# advanced.net
KiCad netlist of a schematic drawn in EAGLE
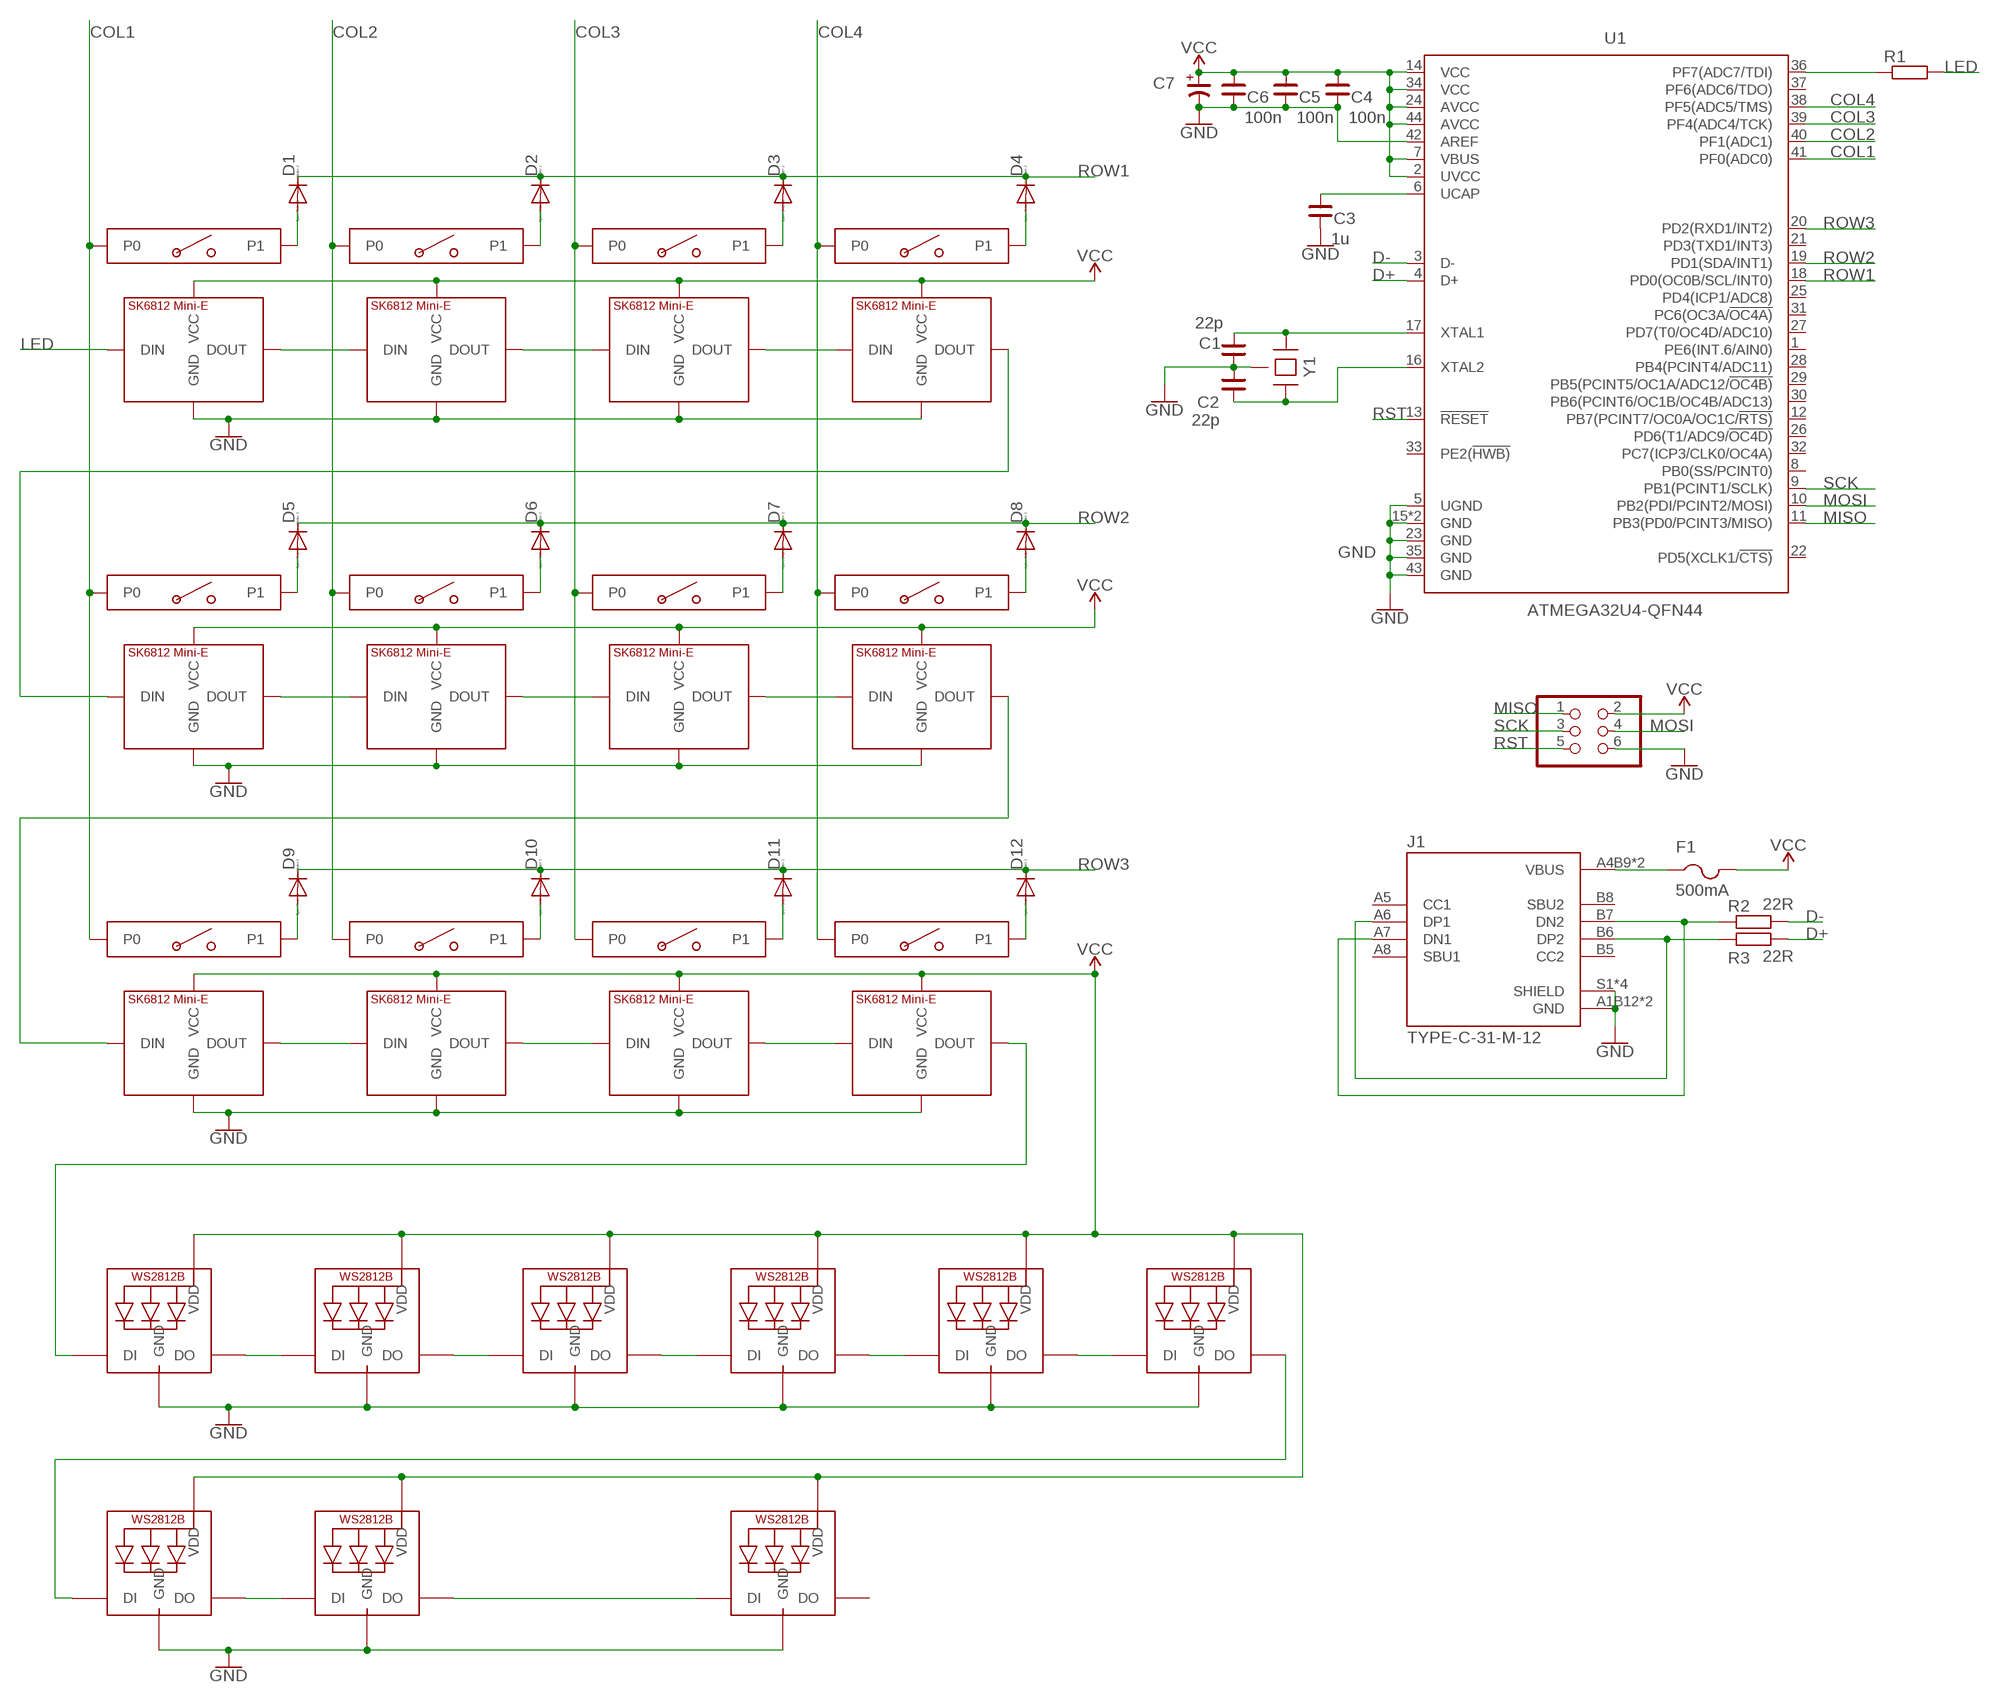
[diagram p0: schematic, sheet 1]

(export (version "E")
  (design (tool "Eeschema 10.0.6"))
  (components
    (comp (ref "C1")
      (value "22p")
      (footprint "eagle-import:0805")
      (libsource (lib "eagle-import") (part "CNP-0805"))
    )
    (comp (ref "C2")
      (value "22p")
      (footprint "eagle-import:0805")
      (libsource (lib "eagle-import") (part "CNP-0805"))
    )
    (comp (ref "C3")
      (value "1u")
      (footprint "eagle-import:0805")
      (libsource (lib "eagle-import") (part "CNP-0805"))
    )
    (comp (ref "C4")
      (value "100n")
      (footprint "eagle-import:0805")
      (libsource (lib "eagle-import") (part "CNP-0805"))
    )
    (comp (ref "C5")
      (value "100n")
      (footprint "eagle-import:0805")
      (libsource (lib "eagle-import") (part "CNP-0805"))
    )
    (comp (ref "C6")
      (value "100n")
      (footprint "eagle-import:0805")
      (libsource (lib "eagle-import") (part "CNP-0805"))
    )
    (comp (ref "C7")
      (value "10u")
      (footprint "eagle-import:3216-18R_T")
      (libsource (lib "eagle-import") (part "CP-3216-18R"))
    )
    (comp (ref "D1")
      (value "1N4148DIODE_0805")
      (footprint "eagle-import:0805")
      (libsource (lib "eagle-import") (part "1N4148DIODE_0805"))
    )
    (comp (ref "D2")
      (value "1N4148DIODE_0805")
      (footprint "eagle-import:0805")
      (libsource (lib "eagle-import") (part "1N4148DIODE_0805"))
    )
    (comp (ref "D3")
      (value "1N4148DIODE_0805")
      (footprint "eagle-import:0805")
      (libsource (lib "eagle-import") (part "1N4148DIODE_0805"))
    )
    (comp (ref "D4")
      (value "1N4148DIODE_0805")
      (footprint "eagle-import:0805")
      (libsource (lib "eagle-import") (part "1N4148DIODE_0805"))
    )
    (comp (ref "D5")
      (value "1N4148DIODE_0805")
      (footprint "eagle-import:0805")
      (libsource (lib "eagle-import") (part "1N4148DIODE_0805"))
    )
    (comp (ref "D6")
      (value "1N4148DIODE_0805")
      (footprint "eagle-import:0805")
      (libsource (lib "eagle-import") (part "1N4148DIODE_0805"))
    )
    (comp (ref "D7")
      (value "1N4148DIODE_0805")
      (footprint "eagle-import:0805")
      (libsource (lib "eagle-import") (part "1N4148DIODE_0805"))
    )
    (comp (ref "D8")
      (value "1N4148DIODE_0805")
      (footprint "eagle-import:0805")
      (libsource (lib "eagle-import") (part "1N4148DIODE_0805"))
    )
    (comp (ref "D9")
      (value "1N4148DIODE_0805")
      (footprint "eagle-import:0805")
      (libsource (lib "eagle-import") (part "1N4148DIODE_0805"))
    )
    (comp (ref "D10")
      (value "1N4148DIODE_0805")
      (footprint "eagle-import:0805")
      (libsource (lib "eagle-import") (part "1N4148DIODE_0805"))
    )
    (comp (ref "D11")
      (value "1N4148DIODE_0805")
      (footprint "eagle-import:0805")
      (libsource (lib "eagle-import") (part "1N4148DIODE_0805"))
    )
    (comp (ref "D12")
      (value "1N4148DIODE_0805")
      (footprint "eagle-import:0805")
      (libsource (lib "eagle-import") (part "1N4148DIODE_0805"))
    )
    (comp (ref "F1")
      (value "500mA")
      (footprint "eagle-import:R1206")
      (libsource (lib "eagle-import") (part "PTCFUSE-1206"))
    )
    (comp (ref "J1")
      (value "TYPE-C-31-M-12")
      (footprint "eagle-import:HRO_TYPE-C-31-M-12")
      (fields (field (name "MF") "HRO Electronics Co., Ltd."))
      (libsource (lib "eagle-import") (part "TYPE-C-31-M-12"))
    )
    (comp (ref "JP3")
      (value "PINHD-2X3")
      (footprint "eagle-import:2X03")
      (libsource (lib "eagle-import") (part "PINHD-2X3"))
    )
    (comp (ref "R1")
      (value "RESISTOR-0805")
      (footprint "eagle-import:R0805")
      (libsource (lib "eagle-import") (part "RESISTOR-0805"))
    )
    (comp (ref "R2")
      (value "22R")
      (footprint "eagle-import:R0805")
      (libsource (lib "eagle-import") (part "RESISTOR-0805"))
    )
    (comp (ref "R3")
      (value "22R")
      (footprint "eagle-import:R0805")
      (libsource (lib "eagle-import") (part "RESISTOR-0805"))
    )
    (comp (ref "U$1")
      (value "WS2812B-3535")
      (footprint "eagle-import:3535-LED")
      (libsource (lib "eagle-import") (part "WS2812B-3535"))
    )
    (comp (ref "U$2")
      (value "WS2812B-3535")
      (footprint "eagle-import:3535-LED")
      (libsource (lib "eagle-import") (part "WS2812B-3535"))
    )
    (comp (ref "U$3")
      (value "WS2812B-3535")
      (footprint "eagle-import:3535-LED")
      (libsource (lib "eagle-import") (part "WS2812B-3535"))
    )
    (comp (ref "U$4")
      (value "WS2812B-3535")
      (footprint "eagle-import:3535-LED")
      (libsource (lib "eagle-import") (part "WS2812B-3535"))
    )
    (comp (ref "U$5")
      (value "WS2812B-3535")
      (footprint "eagle-import:3535-LED")
      (libsource (lib "eagle-import") (part "WS2812B-3535"))
    )
    (comp (ref "U$6")
      (value "WS2812B-3535")
      (footprint "eagle-import:3535-LED")
      (libsource (lib "eagle-import") (part "WS2812B-3535"))
    )
    (comp (ref "U$7")
      (value "WS2812B-3535")
      (footprint "eagle-import:3535-LED")
      (libsource (lib "eagle-import") (part "WS2812B-3535"))
    )
    (comp (ref "U$8")
      (value "WS2812B-3535")
      (footprint "eagle-import:3535-LED")
      (libsource (lib "eagle-import") (part "WS2812B-3535"))
    )
    (comp (ref "U$10")
      (value "WS2812B-3535")
      (footprint "eagle-import:3535-LED")
      (libsource (lib "eagle-import") (part "WS2812B-3535"))
    )
    (comp (ref "U$55")
      (value "KEYSWITCH-SK6812")
      (footprint "eagle-import:UNIVERSAL_KEYSWITCH_SK6812MINIE")
      (libsource (lib "eagle-import") (part "KEYSWITCH-SK6812"))
    )
    (comp (ref "U$57")
      (value "KEYSWITCH-SK6812")
      (footprint "eagle-import:UNIVERSAL_KEYSWITCH_SK6812MINIE")
      (libsource (lib "eagle-import") (part "KEYSWITCH-SK6812"))
    )
    (comp (ref "U$59")
      (value "KEYSWITCH-SK6812")
      (footprint "eagle-import:UNIVERSAL_KEYSWITCH_SK6812MINIE")
      (libsource (lib "eagle-import") (part "KEYSWITCH-SK6812"))
    )
    (comp (ref "U$61")
      (value "KEYSWITCH-SK6812")
      (footprint "eagle-import:UNIVERSAL_KEYSWITCH_SK6812MINIE")
      (libsource (lib "eagle-import") (part "KEYSWITCH-SK6812"))
    )
    (comp (ref "U$73")
      (value "KEYSWITCH-SK6812")
      (footprint "eagle-import:UNIVERSAL_KEYSWITCH_SK6812MINIE")
      (libsource (lib "eagle-import") (part "KEYSWITCH-SK6812"))
    )
    (comp (ref "U$75")
      (value "KEYSWITCH-SK6812")
      (footprint "eagle-import:UNIVERSAL_KEYSWITCH_SK6812MINIE")
      (libsource (lib "eagle-import") (part "KEYSWITCH-SK6812"))
    )
    (comp (ref "U$77")
      (value "KEYSWITCH-SK6812")
      (footprint "eagle-import:UNIVERSAL_KEYSWITCH_SK6812MINIE")
      (libsource (lib "eagle-import") (part "KEYSWITCH-SK6812"))
    )
    (comp (ref "U$79")
      (value "KEYSWITCH-SK6812")
      (footprint "eagle-import:UNIVERSAL_KEYSWITCH_SK6812MINIE")
      (libsource (lib "eagle-import") (part "KEYSWITCH-SK6812"))
    )
    (comp (ref "U$91")
      (value "KEYSWITCH-SK6812")
      (footprint "eagle-import:UNIVERSAL_KEYSWITCH_SK6812MINIE")
      (libsource (lib "eagle-import") (part "KEYSWITCH-SK6812"))
    )
    (comp (ref "U$93")
      (value "KEYSWITCH-SK6812")
      (footprint "eagle-import:UNIVERSAL_KEYSWITCH_SK6812MINIE")
      (libsource (lib "eagle-import") (part "KEYSWITCH-SK6812"))
    )
    (comp (ref "U$95")
      (value "KEYSWITCH-SK6812")
      (footprint "eagle-import:UNIVERSAL_KEYSWITCH_SK6812MINIE")
      (libsource (lib "eagle-import") (part "KEYSWITCH-SK6812"))
    )
    (comp (ref "U$97")
      (value "KEYSWITCH-SK6812")
      (footprint "eagle-import:UNIVERSAL_KEYSWITCH_SK6812MINIE")
      (libsource (lib "eagle-import") (part "KEYSWITCH-SK6812"))
    )
    (comp (ref "U1")
      (value "ATMEGA32U4-QFN44")
      (footprint "eagle-import:QFN-44")
      (libsource (lib "eagle-import") (part "ATMEGA32U4-QFN44"))
    )
    (comp (ref "Y1")
      (value "CRYSTAL-4PIN-3.2X2.5")
      (footprint "eagle-import:CRYSTAL-3.2X2.5")
      (libsource (lib "eagle-import") (part "CRYSTAL-4PIN-3.2X2.5"))
    )
  )
  (nets
    (net (code "1") (name "/COL1") (class "Default")
      (node (ref "U$55") (pin "ALPS1") (pinfunction "P0_ALPS1") (pintype "bidirectional"))
      (node (ref "U$55") (pin "CHOC1") (pinfunction "P0_CHOC1") (pintype "bidirectional"))
      (node (ref "U$55") (pin "MX1") (pinfunction "P0_MX1") (pintype "bidirectional"))
      (node (ref "U$73") (pin "ALPS1") (pinfunction "P0_ALPS1") (pintype "bidirectional"))
      (node (ref "U$73") (pin "CHOC1") (pinfunction "P0_CHOC1") (pintype "bidirectional"))
      (node (ref "U$73") (pin "MX1") (pinfunction "P0_MX1") (pintype "bidirectional"))
      (node (ref "U$91") (pin "ALPS1") (pinfunction "P0_ALPS1") (pintype "bidirectional"))
      (node (ref "U$91") (pin "CHOC1") (pinfunction "P0_CHOC1") (pintype "bidirectional"))
      (node (ref "U$91") (pin "MX1") (pinfunction "P0_MX1") (pintype "bidirectional"))
      (node (ref "U1") (pin "41") (pinfunction "PF0(ADC0)_41") (pintype "bidirectional"))
    )
    (net (code "2") (name "/COL2") (class "Default")
      (node (ref "U$57") (pin "ALPS1") (pinfunction "P0_ALPS1") (pintype "bidirectional"))
      (node (ref "U$57") (pin "CHOC1") (pinfunction "P0_CHOC1") (pintype "bidirectional"))
      (node (ref "U$57") (pin "MX1") (pinfunction "P0_MX1") (pintype "bidirectional"))
      (node (ref "U$75") (pin "ALPS1") (pinfunction "P0_ALPS1") (pintype "bidirectional"))
      (node (ref "U$75") (pin "CHOC1") (pinfunction "P0_CHOC1") (pintype "bidirectional"))
      (node (ref "U$75") (pin "MX1") (pinfunction "P0_MX1") (pintype "bidirectional"))
      (node (ref "U$93") (pin "ALPS1") (pinfunction "P0_ALPS1") (pintype "bidirectional"))
      (node (ref "U$93") (pin "CHOC1") (pinfunction "P0_CHOC1") (pintype "bidirectional"))
      (node (ref "U$93") (pin "MX1") (pinfunction "P0_MX1") (pintype "bidirectional"))
      (node (ref "U1") (pin "40") (pinfunction "PF1(ADC1)_40") (pintype "bidirectional"))
    )
    (net (code "3") (name "/COL3") (class "Default")
      (node (ref "U$59") (pin "ALPS1") (pinfunction "P0_ALPS1") (pintype "bidirectional"))
      (node (ref "U$59") (pin "CHOC1") (pinfunction "P0_CHOC1") (pintype "bidirectional"))
      (node (ref "U$59") (pin "MX1") (pinfunction "P0_MX1") (pintype "bidirectional"))
      (node (ref "U$77") (pin "ALPS1") (pinfunction "P0_ALPS1") (pintype "bidirectional"))
      (node (ref "U$77") (pin "CHOC1") (pinfunction "P0_CHOC1") (pintype "bidirectional"))
      (node (ref "U$77") (pin "MX1") (pinfunction "P0_MX1") (pintype "bidirectional"))
      (node (ref "U$95") (pin "ALPS1") (pinfunction "P0_ALPS1") (pintype "bidirectional"))
      (node (ref "U$95") (pin "CHOC1") (pinfunction "P0_CHOC1") (pintype "bidirectional"))
      (node (ref "U$95") (pin "MX1") (pinfunction "P0_MX1") (pintype "bidirectional"))
      (node (ref "U1") (pin "39") (pinfunction "PF4(ADC4/TCK)_39") (pintype "bidirectional"))
    )
    (net (code "4") (name "/COL4") (class "Default")
      (node (ref "U$61") (pin "ALPS1") (pinfunction "P0_ALPS1") (pintype "bidirectional"))
      (node (ref "U$61") (pin "CHOC1") (pinfunction "P0_CHOC1") (pintype "bidirectional"))
      (node (ref "U$61") (pin "MX1") (pinfunction "P0_MX1") (pintype "bidirectional"))
      (node (ref "U$79") (pin "ALPS1") (pinfunction "P0_ALPS1") (pintype "bidirectional"))
      (node (ref "U$79") (pin "CHOC1") (pinfunction "P0_CHOC1") (pintype "bidirectional"))
      (node (ref "U$79") (pin "MX1") (pinfunction "P0_MX1") (pintype "bidirectional"))
      (node (ref "U$97") (pin "ALPS1") (pinfunction "P0_ALPS1") (pintype "bidirectional"))
      (node (ref "U$97") (pin "CHOC1") (pinfunction "P0_CHOC1") (pintype "bidirectional"))
      (node (ref "U$97") (pin "MX1") (pinfunction "P0_MX1") (pintype "bidirectional"))
      (node (ref "U1") (pin "38") (pinfunction "PF5(ADC5/TMS)_38") (pintype "bidirectional"))
    )
    (net (code "5") (name "/D+") (class "Default")
      (node (ref "R3") (pin "2") (pinfunction "2_2") (pintype "passive"))
      (node (ref "U1") (pin "4") (pinfunction "D+_4") (pintype "bidirectional"))
    )
    (net (code "6") (name "/D-") (class "Default")
      (node (ref "R2") (pin "2") (pinfunction "2_2") (pintype "passive"))
      (node (ref "U1") (pin "3") (pinfunction "D-_3") (pintype "bidirectional"))
    )
    (net (code "7") (name "/LED") (class "Default")
      (node (ref "R1") (pin "2") (pinfunction "2_2") (pintype "passive"))
      (node (ref "U$91") (pin "DIN") (pinfunction "DIN_DIN") (pintype "bidirectional"))
    )
    (net (code "8") (name "/MISO") (class "Default")
      (node (ref "JP3") (pin "1") (pinfunction "1_1") (pintype "passive"))
      (node (ref "U1") (pin "11") (pinfunction "PB3(PD0/PCINT3/MISO)_11") (pintype "bidirectional"))
    )
    (net (code "9") (name "/MOSI") (class "Default")
      (node (ref "JP3") (pin "4") (pinfunction "4_4") (pintype "passive"))
      (node (ref "U1") (pin "10") (pinfunction "PB2(PDI/PCINT2/MOSI)_10") (pintype "bidirectional"))
    )
    (net (code "10") (name "/ROW1") (class "Default")
      (node (ref "D1") (pin "2") (pinfunction "C_2") (pintype "passive"))
      (node (ref "D2") (pin "2") (pinfunction "C_2") (pintype "passive"))
      (node (ref "D3") (pin "2") (pinfunction "C_2") (pintype "passive"))
      (node (ref "D4") (pin "2") (pinfunction "C_2") (pintype "passive"))
      (node (ref "U1") (pin "18") (pinfunction "PD0(OC0B/SCL/INT0)_18") (pintype "bidirectional"))
    )
    (net (code "11") (name "/ROW2") (class "Default")
      (node (ref "D5") (pin "2") (pinfunction "C_2") (pintype "passive"))
      (node (ref "D6") (pin "2") (pinfunction "C_2") (pintype "passive"))
      (node (ref "D7") (pin "2") (pinfunction "C_2") (pintype "passive"))
      (node (ref "D8") (pin "2") (pinfunction "C_2") (pintype "passive"))
      (node (ref "U1") (pin "19") (pinfunction "PD1(SDA/INT1)_19") (pintype "bidirectional"))
    )
    (net (code "12") (name "/ROW3") (class "Default")
      (node (ref "D10") (pin "2") (pinfunction "C_2") (pintype "passive"))
      (node (ref "D11") (pin "2") (pinfunction "C_2") (pintype "passive"))
      (node (ref "D12") (pin "2") (pinfunction "C_2") (pintype "passive"))
      (node (ref "D9") (pin "2") (pinfunction "C_2") (pintype "passive"))
      (node (ref "U1") (pin "20") (pinfunction "PD2(RXD1/INT2)_20") (pintype "bidirectional"))
    )
    (net (code "13") (name "/RST") (class "Default")
      (node (ref "JP3") (pin "5") (pinfunction "5_5") (pintype "passive"))
      (node (ref "U1") (pin "13") (pinfunction "~{RESET}_13") (pintype "bidirectional"))
    )
    (net (code "14") (name "/SCK") (class "Default")
      (node (ref "JP3") (pin "3") (pinfunction "3_3") (pintype "passive"))
      (node (ref "U1") (pin "9") (pinfunction "PB1(PCINT1/SCLK)_9") (pintype "bidirectional"))
    )
    (net (code "15") (name "GND") (class "Default")
      (node (ref "C1") (pin "1") (pinfunction "1_1") (pintype "passive"))
      (node (ref "C2") (pin "2") (pinfunction "2_2") (pintype "passive"))
      (node (ref "C3") (pin "2") (pinfunction "2_2") (pintype "passive"))
      (node (ref "C4") (pin "2") (pinfunction "2_2") (pintype "passive"))
      (node (ref "C5") (pin "2") (pinfunction "2_2") (pintype "passive"))
      (node (ref "C6") (pin "2") (pinfunction "2_2") (pintype "passive"))
      (node (ref "C7") (pin "-") (pinfunction "-_-") (pintype "passive"))
      (node (ref "J1") (pin "A1B12") (pinfunction "GND_A1B12") (pintype "power_in"))
      (node (ref "J1") (pin "B1A12") (pinfunction "GND_B1A12") (pintype "power_in"))
      (node (ref "J1") (pin "S1") (pinfunction "SHIELD_S1") (pintype "passive"))
      (node (ref "J1") (pin "S2") (pinfunction "SHIELD_S2") (pintype "passive"))
      (node (ref "J1") (pin "S3") (pinfunction "SHIELD_S3") (pintype "passive"))
      (node (ref "J1") (pin "S4") (pinfunction "SHIELD_S4") (pintype "passive"))
      (node (ref "JP3") (pin "6") (pinfunction "6_6") (pintype "passive"))
      (node (ref "U$1") (pin "GND") (pinfunction "GND_GND") (pintype "power_in"))
      (node (ref "U$10") (pin "GND") (pinfunction "GND_GND") (pintype "power_in"))
      (node (ref "U$2") (pin "GND") (pinfunction "GND_GND") (pintype "power_in"))
      (node (ref "U$3") (pin "GND") (pinfunction "GND_GND") (pintype "power_in"))
      (node (ref "U$4") (pin "GND") (pinfunction "GND_GND") (pintype "power_in"))
      (node (ref "U$5") (pin "GND") (pinfunction "GND_GND") (pintype "power_in"))
      (node (ref "U$55") (pin "GND") (pinfunction "GND_GND") (pintype "bidirectional"))
      (node (ref "U$57") (pin "GND") (pinfunction "GND_GND") (pintype "bidirectional"))
      (node (ref "U$59") (pin "GND") (pinfunction "GND_GND") (pintype "bidirectional"))
      (node (ref "U$6") (pin "GND") (pinfunction "GND_GND") (pintype "power_in"))
      (node (ref "U$61") (pin "GND") (pinfunction "GND_GND") (pintype "bidirectional"))
      (node (ref "U$7") (pin "GND") (pinfunction "GND_GND") (pintype "power_in"))
      (node (ref "U$73") (pin "GND") (pinfunction "GND_GND") (pintype "bidirectional"))
      (node (ref "U$75") (pin "GND") (pinfunction "GND_GND") (pintype "bidirectional"))
      (node (ref "U$77") (pin "GND") (pinfunction "GND_GND") (pintype "bidirectional"))
      (node (ref "U$79") (pin "GND") (pinfunction "GND_GND") (pintype "bidirectional"))
      (node (ref "U$8") (pin "GND") (pinfunction "GND_GND") (pintype "power_in"))
      (node (ref "U$91") (pin "GND") (pinfunction "GND_GND") (pintype "bidirectional"))
      (node (ref "U$93") (pin "GND") (pinfunction "GND_GND") (pintype "bidirectional"))
      (node (ref "U$95") (pin "GND") (pinfunction "GND_GND") (pintype "bidirectional"))
      (node (ref "U$97") (pin "GND") (pinfunction "GND_GND") (pintype "bidirectional"))
      (node (ref "U1") (pin "15") (pinfunction "GND_15") (pintype "bidirectional"))
      (node (ref "U1") (pin "23") (pinfunction "GND_23") (pintype "bidirectional"))
      (node (ref "U1") (pin "35") (pinfunction "GND_35") (pintype "bidirectional"))
      (node (ref "U1") (pin "42") (pinfunction "AREF_42") (pintype "bidirectional"))
      (node (ref "U1") (pin "43") (pinfunction "GND_43") (pintype "bidirectional"))
      (node (ref "U1") (pin "5") (pinfunction "UGND_5") (pintype "bidirectional"))
      (node (ref "U1") (pin "TAB") (pinfunction "GND_TAB") (pintype "bidirectional"))
      (node (ref "Y1") (pin "2") (pinfunction "GND_2") (pintype "bidirectional"))
      (node (ref "Y1") (pin "4") (pinfunction "GND_4") (pintype "bidirectional"))
    )
    (net (code "16") (name "Net-(D1-A)") (class "Default")
      (node (ref "D1") (pin "1") (pinfunction "A_1") (pintype "passive"))
      (node (ref "U$91") (pin "ALPS2") (pinfunction "P1_ALPS2") (pintype "bidirectional"))
      (node (ref "U$91") (pin "CHOC2") (pinfunction "P1_CHOC2") (pintype "bidirectional"))
      (node (ref "U$91") (pin "MX2") (pinfunction "P1_MX2") (pintype "bidirectional"))
    )
    (net (code "17") (name "Net-(D2-A)") (class "Default")
      (node (ref "D2") (pin "1") (pinfunction "A_1") (pintype "passive"))
      (node (ref "U$93") (pin "ALPS2") (pinfunction "P1_ALPS2") (pintype "bidirectional"))
      (node (ref "U$93") (pin "CHOC2") (pinfunction "P1_CHOC2") (pintype "bidirectional"))
      (node (ref "U$93") (pin "MX2") (pinfunction "P1_MX2") (pintype "bidirectional"))
    )
    (net (code "18") (name "Net-(D3-A)") (class "Default")
      (node (ref "D3") (pin "1") (pinfunction "A_1") (pintype "passive"))
      (node (ref "U$95") (pin "ALPS2") (pinfunction "P1_ALPS2") (pintype "bidirectional"))
      (node (ref "U$95") (pin "CHOC2") (pinfunction "P1_CHOC2") (pintype "bidirectional"))
      (node (ref "U$95") (pin "MX2") (pinfunction "P1_MX2") (pintype "bidirectional"))
    )
    (net (code "19") (name "Net-(D4-A)") (class "Default")
      (node (ref "D4") (pin "1") (pinfunction "A_1") (pintype "passive"))
      (node (ref "U$97") (pin "ALPS2") (pinfunction "P1_ALPS2") (pintype "bidirectional"))
      (node (ref "U$97") (pin "CHOC2") (pinfunction "P1_CHOC2") (pintype "bidirectional"))
      (node (ref "U$97") (pin "MX2") (pinfunction "P1_MX2") (pintype "bidirectional"))
    )
    (net (code "20") (name "Net-(D5-A)") (class "Default")
      (node (ref "D5") (pin "1") (pinfunction "A_1") (pintype "passive"))
      (node (ref "U$73") (pin "ALPS2") (pinfunction "P1_ALPS2") (pintype "bidirectional"))
      (node (ref "U$73") (pin "CHOC2") (pinfunction "P1_CHOC2") (pintype "bidirectional"))
      (node (ref "U$73") (pin "MX2") (pinfunction "P1_MX2") (pintype "bidirectional"))
    )
    (net (code "21") (name "Net-(D6-A)") (class "Default")
      (node (ref "D6") (pin "1") (pinfunction "A_1") (pintype "passive"))
      (node (ref "U$75") (pin "ALPS2") (pinfunction "P1_ALPS2") (pintype "bidirectional"))
      (node (ref "U$75") (pin "CHOC2") (pinfunction "P1_CHOC2") (pintype "bidirectional"))
      (node (ref "U$75") (pin "MX2") (pinfunction "P1_MX2") (pintype "bidirectional"))
    )
    (net (code "22") (name "Net-(D7-A)") (class "Default")
      (node (ref "D7") (pin "1") (pinfunction "A_1") (pintype "passive"))
      (node (ref "U$77") (pin "ALPS2") (pinfunction "P1_ALPS2") (pintype "bidirectional"))
      (node (ref "U$77") (pin "CHOC2") (pinfunction "P1_CHOC2") (pintype "bidirectional"))
      (node (ref "U$77") (pin "MX2") (pinfunction "P1_MX2") (pintype "bidirectional"))
    )
    (net (code "23") (name "Net-(D8-A)") (class "Default")
      (node (ref "D8") (pin "1") (pinfunction "A_1") (pintype "passive"))
      (node (ref "U$79") (pin "ALPS2") (pinfunction "P1_ALPS2") (pintype "bidirectional"))
      (node (ref "U$79") (pin "CHOC2") (pinfunction "P1_CHOC2") (pintype "bidirectional"))
      (node (ref "U$79") (pin "MX2") (pinfunction "P1_MX2") (pintype "bidirectional"))
    )
    (net (code "24") (name "Net-(D9-A)") (class "Default")
      (node (ref "D9") (pin "1") (pinfunction "A_1") (pintype "passive"))
      (node (ref "U$55") (pin "ALPS2") (pinfunction "P1_ALPS2") (pintype "bidirectional"))
      (node (ref "U$55") (pin "CHOC2") (pinfunction "P1_CHOC2") (pintype "bidirectional"))
      (node (ref "U$55") (pin "MX2") (pinfunction "P1_MX2") (pintype "bidirectional"))
    )
    (net (code "25") (name "Net-(D10-A)") (class "Default")
      (node (ref "D10") (pin "1") (pinfunction "A_1") (pintype "passive"))
      (node (ref "U$57") (pin "ALPS2") (pinfunction "P1_ALPS2") (pintype "bidirectional"))
      (node (ref "U$57") (pin "CHOC2") (pinfunction "P1_CHOC2") (pintype "bidirectional"))
      (node (ref "U$57") (pin "MX2") (pinfunction "P1_MX2") (pintype "bidirectional"))
    )
    (net (code "26") (name "Net-(D11-A)") (class "Default")
      (node (ref "D11") (pin "1") (pinfunction "A_1") (pintype "passive"))
      (node (ref "U$59") (pin "ALPS2") (pinfunction "P1_ALPS2") (pintype "bidirectional"))
      (node (ref "U$59") (pin "CHOC2") (pinfunction "P1_CHOC2") (pintype "bidirectional"))
      (node (ref "U$59") (pin "MX2") (pinfunction "P1_MX2") (pintype "bidirectional"))
    )
    (net (code "27") (name "Net-(D12-A)") (class "Default")
      (node (ref "D12") (pin "1") (pinfunction "A_1") (pintype "passive"))
      (node (ref "U$61") (pin "ALPS2") (pinfunction "P1_ALPS2") (pintype "bidirectional"))
      (node (ref "U$61") (pin "CHOC2") (pinfunction "P1_CHOC2") (pintype "bidirectional"))
      (node (ref "U$61") (pin "MX2") (pinfunction "P1_MX2") (pintype "bidirectional"))
    )
    (net (code "28") (name "Net-(F1-Pad1)") (class "Default")
      (node (ref "F1") (pin "1") (pinfunction "1_1") (pintype "passive"))
      (node (ref "J1") (pin "A4B9") (pinfunction "VBUS_A4B9") (pintype "power_in"))
      (node (ref "J1") (pin "B4A9") (pinfunction "VBUS_B4A9") (pintype "power_in"))
    )
    (net (code "29") (name "Net-(J1-DN1)") (class "Default")
      (node (ref "J1") (pin "A7") (pinfunction "DN1_A7") (pintype "bidirectional"))
      (node (ref "J1") (pin "B7") (pinfunction "DN2_B7") (pintype "bidirectional"))
      (node (ref "R2") (pin "1") (pinfunction "1_1") (pintype "passive"))
    )
    (net (code "30") (name "Net-(J1-DP1)") (class "Default")
      (node (ref "J1") (pin "A6") (pinfunction "DP1_A6") (pintype "bidirectional"))
      (node (ref "J1") (pin "B6") (pinfunction "DP2_B6") (pintype "bidirectional"))
      (node (ref "R3") (pin "1") (pinfunction "1_1") (pintype "passive"))
    )
    (net (code "31") (name "Net-(U$1-DI)") (class "Default")
      (node (ref "U$1") (pin "P$3") (pinfunction "DI_P$3") (pintype "input"))
      (node (ref "U$61") (pin "DOUT") (pinfunction "DOUT_DOUT") (pintype "bidirectional"))
    )
    (net (code "32") (name "Net-(U$1-DO)") (class "Default")
      (node (ref "U$1") (pin "P$4") (pinfunction "DO_P$4") (pintype "output"))
      (node (ref "U$2") (pin "P$3") (pinfunction "DI_P$3") (pintype "input"))
    )
    (net (code "33") (name "Net-(U$2-DO)") (class "Default")
      (node (ref "U$2") (pin "P$4") (pinfunction "DO_P$4") (pintype "output"))
      (node (ref "U$3") (pin "P$3") (pinfunction "DI_P$3") (pintype "input"))
    )
    (net (code "34") (name "Net-(U$3-DO)") (class "Default")
      (node (ref "U$3") (pin "P$4") (pinfunction "DO_P$4") (pintype "output"))
      (node (ref "U$4") (pin "P$3") (pinfunction "DI_P$3") (pintype "input"))
    )
    (net (code "35") (name "Net-(U$4-DO)") (class "Default")
      (node (ref "U$4") (pin "P$4") (pinfunction "DO_P$4") (pintype "output"))
      (node (ref "U$5") (pin "P$3") (pinfunction "DI_P$3") (pintype "input"))
    )
    (net (code "36") (name "Net-(U$5-DO)") (class "Default")
      (node (ref "U$5") (pin "P$4") (pinfunction "DO_P$4") (pintype "output"))
      (node (ref "U$6") (pin "P$3") (pinfunction "DI_P$3") (pintype "input"))
    )
    (net (code "37") (name "Net-(U$6-DO)") (class "Default")
      (node (ref "U$6") (pin "P$4") (pinfunction "DO_P$4") (pintype "output"))
      (node (ref "U$7") (pin "P$3") (pinfunction "DI_P$3") (pintype "input"))
    )
    (net (code "38") (name "Net-(U$7-DO)") (class "Default")
      (node (ref "U$7") (pin "P$4") (pinfunction "DO_P$4") (pintype "output"))
      (node (ref "U$8") (pin "P$3") (pinfunction "DI_P$3") (pintype "input"))
    )
    (net (code "39") (name "Net-(U$10-DI)") (class "Default")
      (node (ref "U$10") (pin "P$3") (pinfunction "DI_P$3") (pintype "input"))
      (node (ref "U$8") (pin "P$4") (pinfunction "DO_P$4") (pintype "output"))
    )
    (net (code "40") (name "Net-(U$55-PadDIN)") (class "Default")
      (node (ref "U$55") (pin "DIN") (pinfunction "DIN_DIN") (pintype "bidirectional"))
      (node (ref "U$79") (pin "DOUT") (pinfunction "DOUT_DOUT") (pintype "bidirectional"))
    )
    (net (code "41") (name "Net-(U$55-PadDOUT)") (class "Default")
      (node (ref "U$55") (pin "DOUT") (pinfunction "DOUT_DOUT") (pintype "bidirectional"))
      (node (ref "U$57") (pin "DIN") (pinfunction "DIN_DIN") (pintype "bidirectional"))
    )
    (net (code "42") (name "Net-(U$57-PadDOUT)") (class "Default")
      (node (ref "U$57") (pin "DOUT") (pinfunction "DOUT_DOUT") (pintype "bidirectional"))
      (node (ref "U$59") (pin "DIN") (pinfunction "DIN_DIN") (pintype "bidirectional"))
    )
    (net (code "43") (name "Net-(U$59-PadDOUT)") (class "Default")
      (node (ref "U$59") (pin "DOUT") (pinfunction "DOUT_DOUT") (pintype "bidirectional"))
      (node (ref "U$61") (pin "DIN") (pinfunction "DIN_DIN") (pintype "bidirectional"))
    )
    (net (code "44") (name "Net-(U$73-PadDIN)") (class "Default")
      (node (ref "U$73") (pin "DIN") (pinfunction "DIN_DIN") (pintype "bidirectional"))
      (node (ref "U$97") (pin "DOUT") (pinfunction "DOUT_DOUT") (pintype "bidirectional"))
    )
    (net (code "45") (name "Net-(U$73-PadDOUT)") (class "Default")
      (node (ref "U$73") (pin "DOUT") (pinfunction "DOUT_DOUT") (pintype "bidirectional"))
      (node (ref "U$75") (pin "DIN") (pinfunction "DIN_DIN") (pintype "bidirectional"))
    )
    (net (code "46") (name "Net-(U$75-PadDOUT)") (class "Default")
      (node (ref "U$75") (pin "DOUT") (pinfunction "DOUT_DOUT") (pintype "bidirectional"))
      (node (ref "U$77") (pin "DIN") (pinfunction "DIN_DIN") (pintype "bidirectional"))
    )
    (net (code "47") (name "Net-(U$77-PadDOUT)") (class "Default")
      (node (ref "U$77") (pin "DOUT") (pinfunction "DOUT_DOUT") (pintype "bidirectional"))
      (node (ref "U$79") (pin "DIN") (pinfunction "DIN_DIN") (pintype "bidirectional"))
    )
    (net (code "48") (name "Net-(U$91-PadDOUT)") (class "Default")
      (node (ref "U$91") (pin "DOUT") (pinfunction "DOUT_DOUT") (pintype "bidirectional"))
      (node (ref "U$93") (pin "DIN") (pinfunction "DIN_DIN") (pintype "bidirectional"))
    )
    (net (code "49") (name "Net-(U$93-PadDOUT)") (class "Default")
      (node (ref "U$93") (pin "DOUT") (pinfunction "DOUT_DOUT") (pintype "bidirectional"))
      (node (ref "U$95") (pin "DIN") (pinfunction "DIN_DIN") (pintype "bidirectional"))
    )
    (net (code "50") (name "Net-(U$95-PadDOUT)") (class "Default")
      (node (ref "U$95") (pin "DOUT") (pinfunction "DOUT_DOUT") (pintype "bidirectional"))
      (node (ref "U$97") (pin "DIN") (pinfunction "DIN_DIN") (pintype "bidirectional"))
    )
    (net (code "51") (name "Net-(U1-PF7(ADC7{slash}TDI))") (class "Default")
      (node (ref "R1") (pin "1") (pinfunction "1_1") (pintype "passive"))
      (node (ref "U1") (pin "36") (pinfunction "PF7(ADC7/TDI)_36") (pintype "bidirectional"))
    )
    (net (code "52") (name "Net-(U1-UCAP)") (class "Default")
      (node (ref "C3") (pin "1") (pinfunction "1_1") (pintype "passive"))
      (node (ref "U1") (pin "6") (pinfunction "UCAP_6") (pintype "bidirectional"))
    )
    (net (code "53") (name "Net-(U1-XTAL1)") (class "Default")
      (node (ref "C1") (pin "2") (pinfunction "2_2") (pintype "passive"))
      (node (ref "U1") (pin "17") (pinfunction "XTAL1_17") (pintype "bidirectional"))
      (node (ref "Y1") (pin "1") (pinfunction "1_1") (pintype "passive"))
    )
    (net (code "54") (name "Net-(U1-XTAL2)") (class "Default")
      (node (ref "C2") (pin "1") (pinfunction "1_1") (pintype "passive"))
      (node (ref "U1") (pin "16") (pinfunction "XTAL2_16") (pintype "bidirectional"))
      (node (ref "Y1") (pin "3") (pinfunction "2_3") (pintype "passive"))
    )
    (net (code "55") (name "VCC") (class "Default")
      (node (ref "C4") (pin "1") (pinfunction "1_1") (pintype "passive"))
      (node (ref "C5") (pin "1") (pinfunction "1_1") (pintype "passive"))
      (node (ref "C6") (pin "1") (pinfunction "1_1") (pintype "passive"))
      (node (ref "C7") (pin "+") (pinfunction "+_+") (pintype "passive"))
      (node (ref "F1") (pin "2") (pinfunction "2_2") (pintype "passive"))
      (node (ref "JP3") (pin "2") (pinfunction "2_2") (pintype "passive"))
      (node (ref "U$1") (pin "VDD") (pinfunction "VDD_VDD") (pintype "power_in"))
      (node (ref "U$10") (pin "VDD") (pinfunction "VDD_VDD") (pintype "power_in"))
      (node (ref "U$2") (pin "VDD") (pinfunction "VDD_VDD") (pintype "power_in"))
      (node (ref "U$3") (pin "VDD") (pinfunction "VDD_VDD") (pintype "power_in"))
      (node (ref "U$4") (pin "VDD") (pinfunction "VDD_VDD") (pintype "power_in"))
      (node (ref "U$5") (pin "VDD") (pinfunction "VDD_VDD") (pintype "power_in"))
      (node (ref "U$55") (pin "VCC") (pinfunction "VCC_VCC") (pintype "bidirectional"))
      (node (ref "U$57") (pin "VCC") (pinfunction "VCC_VCC") (pintype "bidirectional"))
      (node (ref "U$59") (pin "VCC") (pinfunction "VCC_VCC") (pintype "bidirectional"))
      (node (ref "U$6") (pin "VDD") (pinfunction "VDD_VDD") (pintype "power_in"))
      (node (ref "U$61") (pin "VCC") (pinfunction "VCC_VCC") (pintype "bidirectional"))
      (node (ref "U$7") (pin "VDD") (pinfunction "VDD_VDD") (pintype "power_in"))
      (node (ref "U$73") (pin "VCC") (pinfunction "VCC_VCC") (pintype "bidirectional"))
      (node (ref "U$75") (pin "VCC") (pinfunction "VCC_VCC") (pintype "bidirectional"))
      (node (ref "U$77") (pin "VCC") (pinfunction "VCC_VCC") (pintype "bidirectional"))
      (node (ref "U$79") (pin "VCC") (pinfunction "VCC_VCC") (pintype "bidirectional"))
      (node (ref "U$8") (pin "VDD") (pinfunction "VDD_VDD") (pintype "power_in"))
      (node (ref "U$91") (pin "VCC") (pinfunction "VCC_VCC") (pintype "bidirectional"))
      (node (ref "U$93") (pin "VCC") (pinfunction "VCC_VCC") (pintype "bidirectional"))
      (node (ref "U$95") (pin "VCC") (pinfunction "VCC_VCC") (pintype "bidirectional"))
      (node (ref "U$97") (pin "VCC") (pinfunction "VCC_VCC") (pintype "bidirectional"))
      (node (ref "U1") (pin "14") (pinfunction "VCC_14") (pintype "bidirectional"))
      (node (ref "U1") (pin "2") (pinfunction "UVCC_2") (pintype "bidirectional"))
      (node (ref "U1") (pin "24") (pinfunction "AVCC_24") (pintype "bidirectional"))
      (node (ref "U1") (pin "34") (pinfunction "VCC_34") (pintype "bidirectional"))
      (node (ref "U1") (pin "44") (pinfunction "AVCC_44") (pintype "bidirectional"))
      (node (ref "U1") (pin "7") (pinfunction "VBUS_7") (pintype "bidirectional"))
    )
    (net (code "56") (name "unconnected-(J1-CC1-PadA5)") (class "Default")
      (node (ref "J1") (pin "A5") (pinfunction "CC1_A5") (pintype "bidirectional"))
    )
    (net (code "57") (name "unconnected-(J1-CC2-PadB5)") (class "Default")
      (node (ref "J1") (pin "B5") (pinfunction "CC2_B5") (pintype "bidirectional"))
    )
    (net (code "58") (name "unconnected-(J1-SBU1-PadA8)") (class "Default")
      (node (ref "J1") (pin "A8") (pinfunction "SBU1_A8") (pintype "bidirectional"))
    )
    (net (code "59") (name "unconnected-(J1-SBU2-PadB8)") (class "Default")
      (node (ref "J1") (pin "B8") (pinfunction "SBU2_B8") (pintype "bidirectional"))
    )
    (net (code "60") (name "unconnected-(U$10-DO-PadP$4)") (class "Default")
      (node (ref "U$10") (pin "P$4") (pinfunction "DO_P$4") (pintype "output"))
    )
    (net (code "61") (name "unconnected-(U1-PB0(SS{slash}PCINT0)-Pad8)") (class "Default")
      (node (ref "U1") (pin "8") (pinfunction "PB0(SS/PCINT0)_8") (pintype "bidirectional"))
    )
    (net (code "62") (name "unconnected-(U1-PB4(PCINT4{slash}ADC11)-Pad28)") (class "Default")
      (node (ref "U1") (pin "28") (pinfunction "PB4(PCINT4/ADC11)_28") (pintype "bidirectional"))
    )
    (net (code "63") (name "unconnected-(U1-PB5(PCINT5{slash}OC1A{slash}ADC12{slash}~{OC4B})-Pad29)") (class "Default")
      (node (ref "U1") (pin "29") (pinfunction "PB5(PCINT5/OC1A/ADC12/~{OC4B})_29") (pintype "bidirectional"))
    )
    (net (code "64") (name "unconnected-(U1-PB6(PCINT6{slash}OC1B{slash}OC4B{slash}ADC13)-Pad30)") (class "Default")
      (node (ref "U1") (pin "30") (pinfunction "PB6(PCINT6/OC1B/OC4B/ADC13)_30") (pintype "bidirectional"))
    )
    (net (code "65") (name "unconnected-(U1-PB7(PCINT7{slash}OC0A{slash}OC1C{slash}~{RTS})-Pad12)") (class "Default")
      (node (ref "U1") (pin "12") (pinfunction "PB7(PCINT7/OC0A/OC1C/~{RTS})_12") (pintype "bidirectional"))
    )
    (net (code "66") (name "unconnected-(U1-PC6(OC3A{slash}~{OC4A})-Pad31)") (class "Default")
      (node (ref "U1") (pin "31") (pinfunction "PC6(OC3A/~{OC4A})_31") (pintype "bidirectional"))
    )
    (net (code "67") (name "unconnected-(U1-PC7(ICP3{slash}CLK0{slash}OC4A)-Pad32)") (class "Default")
      (node (ref "U1") (pin "32") (pinfunction "PC7(ICP3/CLK0/OC4A)_32") (pintype "bidirectional"))
    )
    (net (code "68") (name "unconnected-(U1-PD3(TXD1{slash}INT3)-Pad21)") (class "Default")
      (node (ref "U1") (pin "21") (pinfunction "PD3(TXD1/INT3)_21") (pintype "bidirectional"))
    )
    (net (code "69") (name "unconnected-(U1-PD4(ICP1{slash}ADC8)-Pad25)") (class "Default")
      (node (ref "U1") (pin "25") (pinfunction "PD4(ICP1/ADC8)_25") (pintype "bidirectional"))
    )
    (net (code "70") (name "unconnected-(U1-PD5(XCLK1{slash}~{CTS})-Pad22)") (class "Default")
      (node (ref "U1") (pin "22") (pinfunction "PD5(XCLK1/~{CTS})_22") (pintype "bidirectional"))
    )
    (net (code "71") (name "unconnected-(U1-PD6(T1{slash}ADC9{slash}~{OC4D})-Pad26)") (class "Default")
      (node (ref "U1") (pin "26") (pinfunction "PD6(T1/ADC9/~{OC4D})_26") (pintype "bidirectional"))
    )
    (net (code "72") (name "unconnected-(U1-PD7(T0{slash}OC4D{slash}ADC10)-Pad27)") (class "Default")
      (node (ref "U1") (pin "27") (pinfunction "PD7(T0/OC4D/ADC10)_27") (pintype "bidirectional"))
    )
    (net (code "73") (name "unconnected-(U1-PE2(~{HWB})-Pad33)") (class "Default")
      (node (ref "U1") (pin "33") (pinfunction "PE2(~{HWB})_33") (pintype "bidirectional"))
    )
    (net (code "74") (name "unconnected-(U1-PE6(INT.6{slash}AIN0)-Pad1)") (class "Default")
      (node (ref "U1") (pin "1") (pinfunction "PE6(INT.6/AIN0)_1") (pintype "bidirectional"))
    )
    (net (code "75") (name "unconnected-(U1-PF6(ADC6{slash}TDO)-Pad37)") (class "Default")
      (node (ref "U1") (pin "37") (pinfunction "PF6(ADC6/TDO)_37") (pintype "bidirectional"))
    )
  )
)
